# ATMega48_Breakout.net
KiCad netlist of a schematic drawn in EAGLE
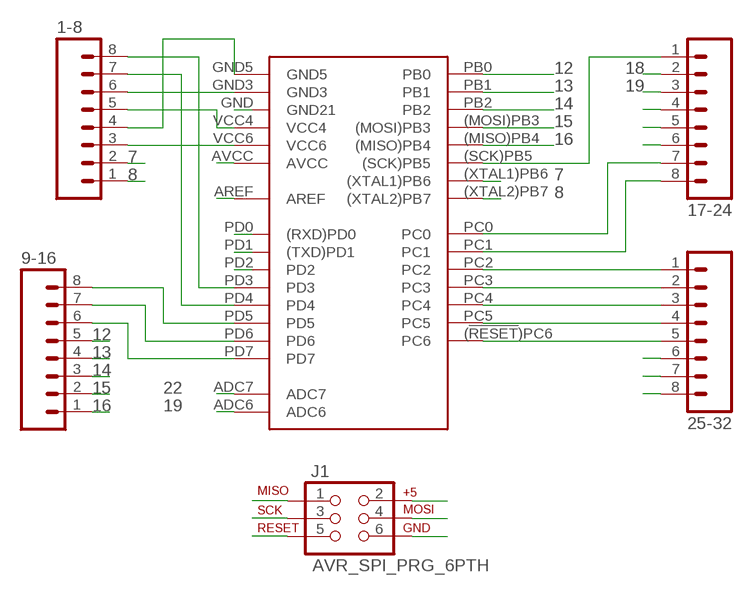
[diagram p0: schematic, sheet 1]

(export (version "E")
  (design (tool "Eeschema 10.0.6"))
  (components
    (comp (ref "1-8")
      (value "M081X08")
      (footprint "eagle-import:1X08")
      (libsource (lib "eagle-import") (part "M081X08"))
    )
    (comp (ref "9-16")
      (value "M081X08")
      (footprint "eagle-import:1X08")
      (libsource (lib "eagle-import") (part "M081X08"))
    )
    (comp (ref "17-24")
      (value "M081X08")
      (footprint "eagle-import:1X08")
      (libsource (lib "eagle-import") (part "M081X08"))
    )
    (comp (ref "25-32")
      (value "M081X08")
      (footprint "eagle-import:1X08")
      (libsource (lib "eagle-import") (part "M081X08"))
    )
    (comp (ref "J1")
      (value "AVR_SPI_PRG_6PTH")
      (footprint "eagle-import:2X3")
      (libsource (lib "eagle-import") (part "AVR_SPI_PRG_6PTH"))
    )
    (comp (ref "MAIN")
      (value "ATMEGA48")
      (footprint "eagle-import:TQFP-32")
      (libsource (lib "eagle-import") (part "ATMEGA48"))
    )
  )
  (nets
    (net (code "1") (name "/3") (class "Default")
      (node (ref "1-8") (pin "6") (pinfunction "6_6") (pintype "passive"))
      (node (ref "J1") (pin "6") (pinfunction "6_6") (pintype "passive"))
      (node (ref "MAIN") (pin "GND3") (pinfunction "GND3_GND3") (pintype "bidirectional"))
    )
    (net (code "2") (name "/4") (class "Default")
      (node (ref "1-8") (pin "5") (pinfunction "5_5") (pintype "passive"))
      (node (ref "J1") (pin "2") (pinfunction "2_2") (pintype "passive"))
      (node (ref "MAIN") (pin "VCC4") (pinfunction "VCC4_VCC4") (pintype "bidirectional"))
    )
    (net (code "3") (name "/7") (class "Default")
      (node (ref "1-8") (pin "2") (pinfunction "2_2") (pintype "passive"))
      (node (ref "MAIN") (pin "(XTAL1)PB6") (pinfunction "(XTAL1)PB6_(XTAL1)PB6") (pintype "bidirectional"))
    )
    (net (code "4") (name "/8") (class "Default")
      (node (ref "1-8") (pin "1") (pinfunction "1_1") (pintype "passive"))
      (node (ref "MAIN") (pin "(XTAL2)PB7") (pinfunction "(XTAL2)PB7_(XTAL2)PB7") (pintype "bidirectional"))
    )
    (net (code "5") (name "/12") (class "Default")
      (node (ref "9-16") (pin "5") (pinfunction "5_5") (pintype "passive"))
      (node (ref "MAIN") (pin "PB0") (pinfunction "PB0_PB0") (pintype "bidirectional"))
    )
    (net (code "6") (name "/13") (class "Default")
      (node (ref "9-16") (pin "4") (pinfunction "4_4") (pintype "passive"))
      (node (ref "MAIN") (pin "PB1") (pinfunction "PB1_PB1") (pintype "bidirectional"))
    )
    (net (code "7") (name "/14") (class "Default")
      (node (ref "9-16") (pin "3") (pinfunction "3_3") (pintype "passive"))
      (node (ref "MAIN") (pin "PB2") (pinfunction "PB2_PB2") (pintype "bidirectional"))
    )
    (net (code "8") (name "/15") (class "Default")
      (node (ref "9-16") (pin "2") (pinfunction "2_2") (pintype "passive"))
      (node (ref "J1") (pin "4") (pinfunction "4_4") (pintype "passive"))
      (node (ref "MAIN") (pin "(MOSI)PB3") (pinfunction "(MOSI)PB3_(MOSI)PB3") (pintype "bidirectional"))
    )
    (net (code "9") (name "/16") (class "Default")
      (node (ref "9-16") (pin "1") (pinfunction "1_1") (pintype "passive"))
      (node (ref "J1") (pin "1") (pinfunction "1_1") (pintype "passive"))
      (node (ref "MAIN") (pin "(MISO)PB4") (pinfunction "(MISO)PB4_(MISO)PB4") (pintype "bidirectional"))
    )
    (net (code "10") (name "/17") (class "Default")
      (node (ref "17-24") (pin "1") (pinfunction "1_1") (pintype "passive"))
      (node (ref "J1") (pin "3") (pinfunction "3_3") (pintype "passive"))
      (node (ref "MAIN") (pin "(SCK)PB5") (pinfunction "(SCK)PB5_(SCK)PB5") (pintype "bidirectional"))
    )
    (net (code "11") (name "/18") (class "Default")
      (node (ref "17-24") (pin "2") (pinfunction "2_2") (pintype "passive"))
      (node (ref "MAIN") (pin "AVCC") (pinfunction "AVCC_AVCC") (pintype "bidirectional"))
    )
    (net (code "12") (name "/19") (class "Default")
      (node (ref "17-24") (pin "3") (pinfunction "3_3") (pintype "passive"))
      (node (ref "MAIN") (pin "ADC6") (pinfunction "ADC6_ADC6") (pintype "bidirectional"))
    )
    (net (code "13") (name "/20") (class "Default")
      (node (ref "17-24") (pin "4") (pinfunction "4_4") (pintype "passive"))
      (node (ref "MAIN") (pin "AREF") (pinfunction "AREF_AREF") (pintype "bidirectional"))
    )
    (net (code "14") (name "/21") (class "Default")
      (node (ref "17-24") (pin "5") (pinfunction "5_5") (pintype "passive"))
      (node (ref "MAIN") (pin "GND") (pinfunction "GND21_GND") (pintype "bidirectional"))
    )
    (net (code "15") (name "/22") (class "Default")
      (node (ref "17-24") (pin "6") (pinfunction "6_6") (pintype "passive"))
      (node (ref "MAIN") (pin "ADC7") (pinfunction "ADC7_ADC7") (pintype "bidirectional"))
    )
    (net (code "16") (name "/29") (class "Default")
      (node (ref "25-32") (pin "5") (pinfunction "5_5") (pintype "passive"))
      (node (ref "J1") (pin "5") (pinfunction "5_5") (pintype "passive"))
      (node (ref "MAIN") (pin "(!RESET!)PC6") (pinfunction "PC6_(!RESET!)PC6") (pintype "bidirectional"))
    )
    (net (code "17") (name "/30") (class "Default")
      (node (ref "25-32") (pin "6") (pinfunction "6_6") (pintype "passive"))
      (node (ref "MAIN") (pin "PD0") (pinfunction "(RXD)PD0_PD0") (pintype "bidirectional"))
    )
    (net (code "18") (name "/31") (class "Default")
      (node (ref "25-32") (pin "7") (pinfunction "7_7") (pintype "passive"))
      (node (ref "MAIN") (pin "PD1") (pinfunction "(TXD)PD1_PD1") (pintype "bidirectional"))
    )
    (net (code "19") (name "/32") (class "Default")
      (node (ref "25-32") (pin "8") (pinfunction "8_8") (pintype "passive"))
      (node (ref "MAIN") (pin "PD2") (pinfunction "PD2_PD2") (pintype "bidirectional"))
    )
    (net (code "20") (name "Net-(1-8-Pad3)") (class "Default")
      (node (ref "1-8") (pin "3") (pinfunction "3_3") (pintype "passive"))
      (node (ref "MAIN") (pin "VCC6") (pinfunction "VCC6_VCC6") (pintype "bidirectional"))
    )
    (net (code "21") (name "Net-(1-8-Pad4)") (class "Default")
      (node (ref "1-8") (pin "4") (pinfunction "4_4") (pintype "passive"))
      (node (ref "MAIN") (pin "GND5") (pinfunction "GND5_GND5") (pintype "bidirectional"))
    )
    (net (code "22") (name "Net-(1-8-Pad7)") (class "Default")
      (node (ref "1-8") (pin "7") (pinfunction "7_7") (pintype "passive"))
      (node (ref "MAIN") (pin "PD4") (pinfunction "PD4_PD4") (pintype "bidirectional"))
    )
    (net (code "23") (name "Net-(1-8-Pad8)") (class "Default")
      (node (ref "1-8") (pin "8") (pinfunction "8_8") (pintype "passive"))
      (node (ref "MAIN") (pin "PD3") (pinfunction "PD3_PD3") (pintype "bidirectional"))
    )
    (net (code "24") (name "Net-(9-16-Pad6)") (class "Default")
      (node (ref "9-16") (pin "6") (pinfunction "6_6") (pintype "passive"))
      (node (ref "MAIN") (pin "PD7") (pinfunction "PD7_PD7") (pintype "bidirectional"))
    )
    (net (code "25") (name "Net-(9-16-Pad7)") (class "Default")
      (node (ref "9-16") (pin "7") (pinfunction "7_7") (pintype "passive"))
      (node (ref "MAIN") (pin "PD6") (pinfunction "PD6_PD6") (pintype "bidirectional"))
    )
    (net (code "26") (name "Net-(9-16-Pad8)") (class "Default")
      (node (ref "9-16") (pin "8") (pinfunction "8_8") (pintype "passive"))
      (node (ref "MAIN") (pin "PD5") (pinfunction "PD5_PD5") (pintype "bidirectional"))
    )
    (net (code "27") (name "Net-(17-24-Pad7)") (class "Default")
      (node (ref "17-24") (pin "7") (pinfunction "7_7") (pintype "passive"))
      (node (ref "MAIN") (pin "PC0") (pinfunction "PC0_PC0") (pintype "bidirectional"))
    )
    (net (code "28") (name "Net-(17-24-Pad8)") (class "Default")
      (node (ref "17-24") (pin "8") (pinfunction "8_8") (pintype "passive"))
      (node (ref "MAIN") (pin "PC1") (pinfunction "PC1_PC1") (pintype "bidirectional"))
    )
    (net (code "29") (name "Net-(25-32-Pad1)") (class "Default")
      (node (ref "25-32") (pin "1") (pinfunction "1_1") (pintype "passive"))
      (node (ref "MAIN") (pin "PC2") (pinfunction "PC2_PC2") (pintype "bidirectional"))
    )
    (net (code "30") (name "Net-(25-32-Pad2)") (class "Default")
      (node (ref "25-32") (pin "2") (pinfunction "2_2") (pintype "passive"))
      (node (ref "MAIN") (pin "PC3") (pinfunction "PC3_PC3") (pintype "bidirectional"))
    )
    (net (code "31") (name "Net-(25-32-Pad3)") (class "Default")
      (node (ref "25-32") (pin "3") (pinfunction "3_3") (pintype "passive"))
      (node (ref "MAIN") (pin "PC4") (pinfunction "PC4_PC4") (pintype "bidirectional"))
    )
    (net (code "32") (name "Net-(25-32-Pad4)") (class "Default")
      (node (ref "25-32") (pin "4") (pinfunction "4_4") (pintype "passive"))
      (node (ref "MAIN") (pin "PC5") (pinfunction "PC5_PC5") (pintype "bidirectional"))
    )
  )
)
